# VCSEL.net
KiCad netlist of a schematic drawn in Altium Designer
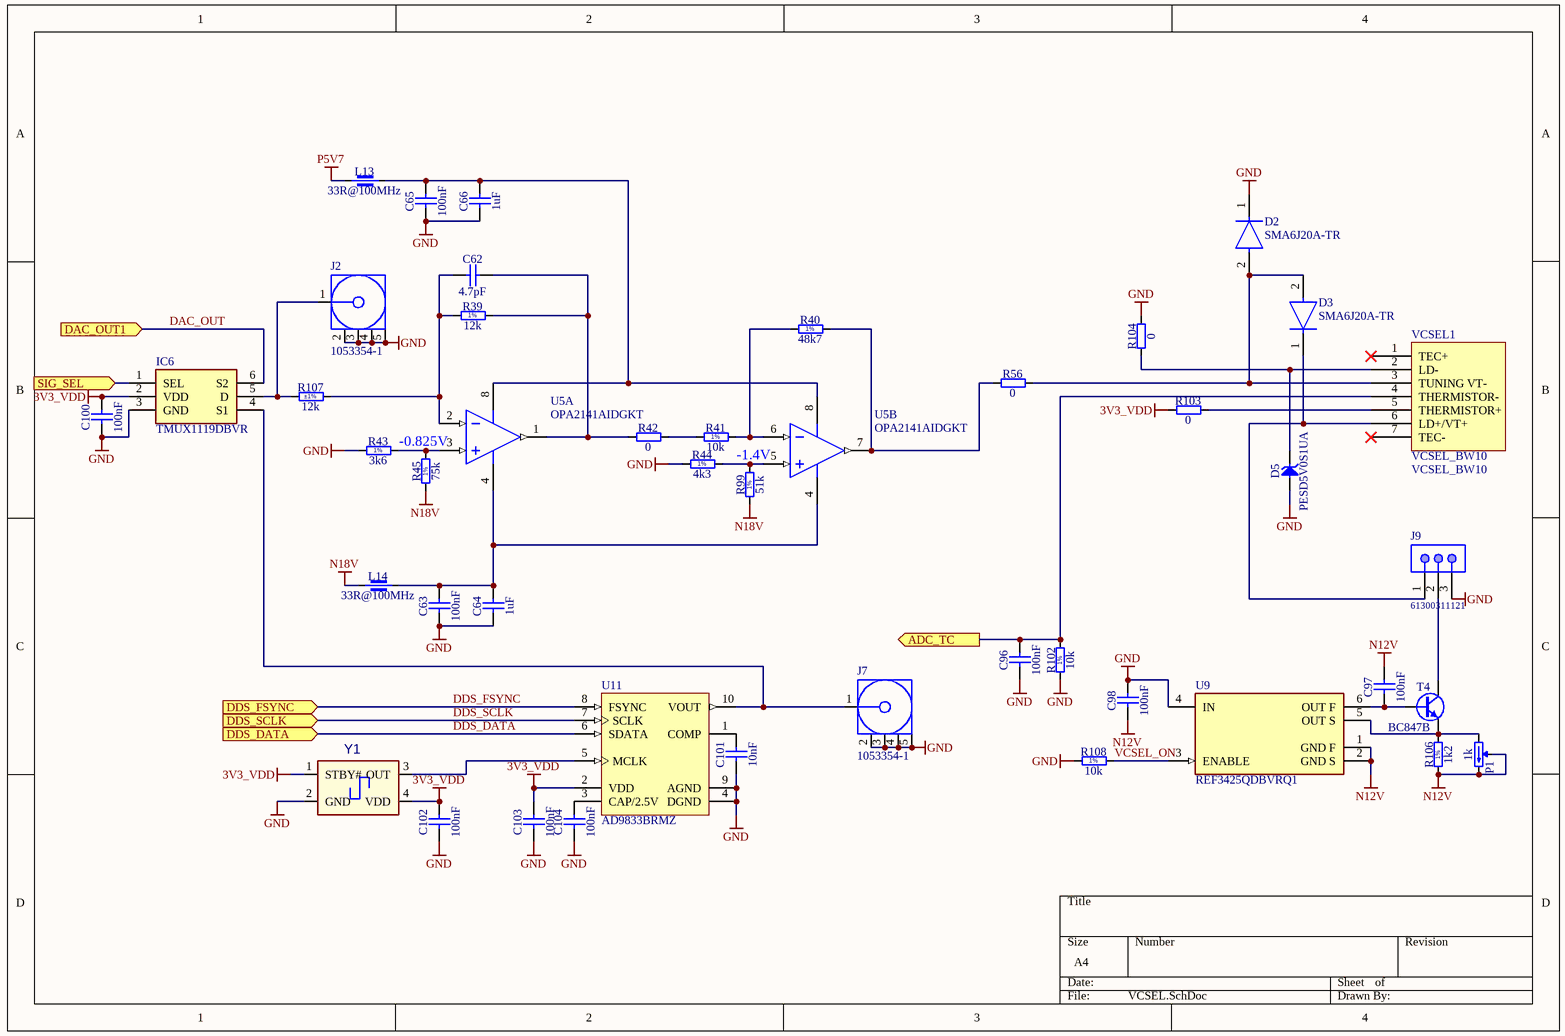
[diagram p0: VCSEL.SchDoc]

(export (version "E")
  (design (tool "Eeschema 10.0.6"))
  (components
    (comp (ref "C62")
      (value "4.7pF")
      (footprint "CAPC1005X70N")
      (description "Non-polarised capacitor")
      (fields
        (field (name "PART NUMBER") "CC0402_4.7PF_50V_0.25PF_C0G_VISHAY_VJ_NON-MAGNETIC")
        (field (name "VOLTAGE") "50V")
        (field (name "AUTHOR") "CERN DEM MR")
      )
      (libsource (lib "Capacitors") (part "Capacitor - non polarized"))
    )
    (comp (ref "C63")
      (value "100nF")
      (footprint "CAPC1608X87N")
      (description "Non-polarised capacitor")
      (fields
        (field (name "PART NUMBER") "CC0603_100NF_50V_10%_X5R")
        (field (name "VOLTAGE") "50V")
        (field (name "AUTHOR") "CERN DEM MR")
      )
      (libsource (lib "Capacitors") (part "Capacitor - non polarized"))
    )
    (comp (ref "C64")
      (value "1uF")
      (footprint "CAPC1608X87N")
      (description "Non-polarised capacitor")
      (fields
        (field (name "PART NUMBER") "CC0603_1UF_25V_10%_X7R")
        (field (name "VOLTAGE") "25V")
        (field (name "AUTHOR") "CERN DEM JLC")
      )
      (libsource (lib "Capacitors") (part "Capacitor - non polarized"))
    )
    (comp (ref "C65")
      (value "100nF")
      (footprint "CAPC1005X55N")
      (description "Non-polarised capacitor")
      (fields
        (field (name "PART NUMBER") "CC0402_100NF_16V_10%_X7R")
        (field (name "VOLTAGE") "16V")
        (field (name "AUTHOR") "CERN DEM JLC")
      )
      (libsource (lib "Capacitors") (part "Capacitor - non polarized"))
    )
    (comp (ref "C66")
      (value "1uF")
      (footprint "CAPC1005X55N")
      (description "Non-polarised capacitor")
      (fields
        (field (name "PART NUMBER") "CC0402_1UF_16V_10%_X5R")
        (field (name "VOLTAGE") "16V")
        (field (name "AUTHOR") "CERN DEM JLC")
      )
      (libsource (lib "Capacitors") (part "Capacitor - non polarized"))
    )
    (comp (ref "C96")
      (value "100nF")
      (footprint "CAPC1005X55N")
      (description "Non-polarised capacitor")
      (fields
        (field (name "PART NUMBER") "CC0402_100NF_16V_10%_X7R")
        (field (name "VOLTAGE") "16V")
        (field (name "AUTHOR") "CERN DEM JLC")
      )
      (libsource (lib "Capacitors") (part "Capacitor - non polarized"))
    )
    (comp (ref "C97")
      (value "100nF")
      (footprint "CAPC1005X55N")
      (description "Non-polarised capacitor")
      (fields
        (field (name "PART NUMBER") "CC0402_100NF_16V_10%_X7R")
        (field (name "VOLTAGE") "16V")
        (field (name "AUTHOR") "CERN DEM JLC")
      )
      (libsource (lib "Capacitors") (part "Capacitor - non polarized"))
    )
    (comp (ref "C98")
      (value "100nF")
      (footprint "CAPC1005X55N")
      (description "Non-polarised capacitor")
      (fields
        (field (name "PART NUMBER") "CC0402_100NF_16V_10%_X7R")
        (field (name "VOLTAGE") "16V")
        (field (name "AUTHOR") "CERN DEM JLC")
      )
      (libsource (lib "Capacitors") (part "Capacitor - non polarized"))
    )
    (comp (ref "C100")
      (value "100nF")
      (footprint "CAPC1005X55N")
      (description "Non-polarised capacitor")
      (fields
        (field (name "PART NUMBER") "CC0402_100NF_16V_10%_X7R")
        (field (name "VOLTAGE") "16V")
        (field (name "AUTHOR") "CERN DEM JLC")
      )
      (libsource (lib "Capacitors") (part "Capacitor - non polarized"))
    )
    (comp (ref "C101")
      (value "10nF")
      (footprint "CAPC1005X55N")
      (description "Non-polarised capacitor")
      (fields
        (field (name "PART NUMBER") "CC0402_10NF_16V_10%_X7R")
        (field (name "VOLTAGE") "16V")
        (field (name "AUTHOR") "CERN DEM JLC")
      )
      (libsource (lib "Capacitors") (part "Capacitor - non polarized"))
    )
    (comp (ref "C102")
      (value "100nF")
      (footprint "CAPC1005X55N")
      (description "Non-polarised capacitor")
      (fields
        (field (name "PART NUMBER") "CC0402_100NF_16V_10%_X7R")
        (field (name "VOLTAGE") "16V")
        (field (name "AUTHOR") "CERN DEM JLC")
      )
      (libsource (lib "Capacitors") (part "Capacitor - non polarized"))
    )
    (comp (ref "C103")
      (value "100nF")
      (footprint "CAPC1005X55N")
      (description "Non-polarised capacitor")
      (fields
        (field (name "PART NUMBER") "CC0402_100NF_16V_10%_X7R")
        (field (name "VOLTAGE") "16V")
        (field (name "AUTHOR") "CERN DEM JLC")
      )
      (libsource (lib "Capacitors") (part "Capacitor - non polarized"))
    )
    (comp (ref "C104")
      (value "100nF")
      (footprint "CAPC1005X55N")
      (description "Non-polarised capacitor")
      (fields
        (field (name "PART NUMBER") "CC0402_100NF_16V_10%_X7R")
        (field (name "VOLTAGE") "16V")
        (field (name "AUTHOR") "CERN DEM JLC")
      )
      (libsource (lib "Capacitors") (part "Capacitor - non polarized"))
    )
    (comp (ref "D2")
      (value "SMA6J20A-TR")
      (footprint "FP-SMA-MFG")
      (description "TVS DIODE 20V 36.8V SMA")
      (libsource (lib "Altium Content Vault") (part "d7152d700b627762746794eb795d46e"))
    )
    (comp (ref "D3")
      (value "SMA6J20A-TR")
      (footprint "FP-SMA-MFG")
      (description "TVS DIODE 20V 36.8V SMA")
      (libsource (lib "Altium Content Vault") (part "d7152d700b627762746794eb795d46e"))
    )
    (comp (ref "D5")
      (value "PESD5V0S1UA")
      (footprint "SOD2512X110N")
      (description "Transient Voltage Suppressor Diode (Uni-Directional)")
      (fields
        (field (name "VOLTAGE") "5V")
        (field (name "POWER") "890W")
        (field (name "AUTHOR") "CERN DEM JLC")
      )
      (libsource (lib "ICs And Semiconductors") (part "Diode TVS Uni-Directional"))
    )
    (comp (ref "IC6")
      (value "TMUX1119DBVR")
      (footprint "SamacSys:SOT95P280X145-6N")
      (description "Integrated Circuit")
      (libsource (lib "*") (part "TMUX1119DBVR"))
    )
    (comp (ref "J2")
      (value "1053354-1")
      (footprint "TECO-1053354-1_V")
      (description "Female Coaxial Connector, Pitch 2.55 mm, Height 9.5 mm, Tail Length 3.9 mm, RoHS, Bulk")
      (fields (field (name "MANUFACTURER") "TE Connectivity"))
      (libsource (lib "Altium Content Vault") (part "CN-S-4F-RF5"))
    )
    (comp (ref "J7")
      (value "1053354-1")
      (footprint "TECO-1053354-1_V")
      (description "Female Coaxial Connector, Pitch 2.55 mm, Height 9.5 mm, Tail Length 3.9 mm, RoHS, Bulk")
      (fields (field (name "MANUFACTURER") "TE Connectivity"))
      (libsource (lib "Altium Content Vault") (part "CN-S-4F-RF5"))
    )
    (comp (ref "J9")
      (value "61300311121")
      (footprint "61300311121")
      (description "WR-PHD Pin Header, THT, pitch 2.54mm, Single Row, Vertical, 3pin")
      (fields (field (name "PUBLISHER") "Wurth Elektronik"))
      (libsource (lib "ALTIUM-WR-PHD_PIN_HEADER_SOCKET_HEADER-rev19a") (part "61300311121"))
    )
    (comp (ref "L13")
      (value "33R@100MHz")
      (footprint "INDC1005X55N")
      (fields
        (field (name "PART NUMBER") "IND0402_MURATA_BLM15PX330SN1D")
        (field (name "POWER") "3A")
        (field (name "TOLERANCE") "±25%")
        (field (name "AUTHOR") "CERN DEM JMW")
      )
      (libsource (lib "Inductors & Transformers") (part "Ferrite Bead"))
    )
    (comp (ref "L14")
      (value "33R@100MHz")
      (footprint "INDC1005X55N")
      (fields
        (field (name "PART NUMBER") "IND0402_MURATA_BLM15PX330SN1D")
        (field (name "POWER") "3A")
        (field (name "TOLERANCE") "±25%")
        (field (name "AUTHOR") "CERN DEM JMW")
      )
      (libsource (lib "Inductors & Transformers") (part "Ferrite Bead"))
    )
    (comp (ref "P1")
      (value "1k")
      (footprint "TRIM_BOURNS_3266W")
      (description "Trimming Potentiometer")
      (fields
        (field (name "PART NUMBER") "TRIM_12T_1K_BOURNS_3266W-1-102LF")
        (field (name "POWER") "0.25W")
        (field (name "AUTHOR") "CERN DEM JLC")
      )
      (libsource (lib "Resistors") (part "Trimming Potentiometer"))
    )
    (comp (ref "R39")
      (value "12k")
      (footprint "RESC1005X40N")
      (description "Resistor - 1%")
      (fields
        (field (name "PART NUMBER") "R0402_12K_1%_0.0625W_100PPM")
        (field (name "POWER") "0.0625W")
        (field (name "AUTHOR") "CERN DEM JLC")
      )
      (libsource (lib "Resistors") (part "Resistor - 1%"))
    )
    (comp (ref "R40")
      (value "48k7")
      (footprint "RESC1608X55N")
      (description "Resistor - 1%")
      (fields
        (field (name "PART NUMBER") "R0603_48K7_1%_0.1W_100PPM")
        (field (name "POWER") "0.1W")
        (field (name "AUTHOR") "CERN DEM JLC")
      )
      (libsource (lib "") (part "Resistor - 1%_1"))
    )
    (comp (ref "R41")
      (value "10k")
      (footprint "RESC1005X40N")
      (description "Resistor - 1%")
      (fields
        (field (name "PART NUMBER") "R0402_10K_1%_0.0625W_100PPM")
        (field (name "POWER") "0.0625W")
        (field (name "AUTHOR") "CERN DEM JLC")
      )
      (libsource (lib "Resistors") (part "Resistor - 1%"))
    )
    (comp (ref "R42")
      (value "0")
      (footprint "RESC1005X40N")
      (description "Resistor")
      (fields
        (field (name "PART NUMBER") "R0402_0R_JUMPER")
        (field (name "MANUFACTURER") "GENERIC")
        (field (name "AUTHOR") "CERN DEM JLC")
      )
      (libsource (lib "Resistors") (part "Resistor"))
    )
    (comp (ref "R43")
      (value "3k6")
      (footprint "RESC1005X40N")
      (description "Resistor - 1%")
      (fields
        (field (name "PART NUMBER") "R0402_3K6_1%_0.0625W_100PPM")
        (field (name "POWER") "0.0625W")
        (field (name "AUTHOR") "CERN DEM JLC")
      )
      (libsource (lib "Resistors") (part "Resistor - 1%"))
    )
    (comp (ref "R44")
      (value "4k3")
      (footprint "RESC1005X40N")
      (description "Resistor - 1%")
      (fields
        (field (name "PART NUMBER") "R0402_4K3_1%_0.0625W_100PPM")
        (field (name "POWER") "0.0625W")
        (field (name "AUTHOR") "CERN DEM JLC")
      )
      (libsource (lib "Resistors") (part "Resistor - 1%"))
    )
    (comp (ref "R45")
      (value "75k")
      (footprint "RESC1005X40N")
      (description "Resistor - 1%")
      (fields
        (field (name "PART NUMBER") "R0402_75K_1%_0.0625W_100PPM")
        (field (name "POWER") "0.0625W")
        (field (name "AUTHOR") "CERN DEM JLC")
      )
      (libsource (lib "Resistors") (part "Resistor - 1%"))
    )
    (comp (ref "R56")
      (value "0")
      (footprint "RESC1005X40N")
      (description "Resistor")
      (fields
        (field (name "PART NUMBER") "R0402_0R_JUMPER")
        (field (name "MANUFACTURER") "GENERIC")
        (field (name "AUTHOR") "CERN DEM JLC")
      )
      (libsource (lib "Resistors") (part "Resistor"))
    )
    (comp (ref "R99")
      (value "51k")
      (footprint "RESC1005X40N")
      (description "Resistor - 1%")
      (fields
        (field (name "PART NUMBER") "R0402_51K_1%_0.0625W_100PPM")
        (field (name "POWER") "0.0625W")
        (field (name "AUTHOR") "CERN DEM JLC")
      )
      (libsource (lib "Resistors") (part "Resistor - 1%"))
    )
    (comp (ref "R102")
      (value "10k")
      (footprint "RESC1005X40N")
      (description "Resistor - 1%")
      (fields
        (field (name "PART NUMBER") "R0402_10K_1%_0.0625W_100PPM")
        (field (name "POWER") "0.0625W")
        (field (name "AUTHOR") "CERN DEM JLC")
      )
      (libsource (lib "Resistors") (part "Resistor - 1%"))
    )
    (comp (ref "R103")
      (value "0")
      (footprint "RESC1005X40N")
      (description "Resistor")
      (fields
        (field (name "PART NUMBER") "R0402_0R_JUMPER")
        (field (name "MANUFACTURER") "GENERIC")
        (field (name "AUTHOR") "CERN DEM JLC")
      )
      (libsource (lib "Resistors") (part "Resistor"))
    )
    (comp (ref "R104")
      (value "0")
      (footprint "RESC1005X40N")
      (description "Resistor")
      (fields
        (field (name "PART NUMBER") "R0402_0R_JUMPER")
        (field (name "MANUFACTURER") "GENERIC")
        (field (name "AUTHOR") "CERN DEM JLC")
      )
      (libsource (lib "Resistors") (part "Resistor"))
    )
    (comp (ref "R106")
      (value "1k2")
      (footprint "RESC1005X40N")
      (description "Resistor - 1%")
      (fields
        (field (name "PART NUMBER") "R0402_1K2_1%_0.0625W_100PPM")
        (field (name "POWER") "0.0625W")
        (field (name "AUTHOR") "CERN DEM JLC")
      )
      (libsource (lib "Resistors") (part "Resistor - 1%"))
    )
    (comp (ref "R107")
      (value "12k")
      (footprint "RESC1005X40N")
      (description "Resistor - 1%")
      (fields
        (field (name "PART NUMBER") "R0402_12K_1%_0.0625W_100PPM")
        (field (name "MANUFACTURER") "GENERIC")
        (field (name "TOLERANCE") "±1%")
        (field (name "AUTHOR") "CERN DEM JLC")
      )
      (libsource (lib "Resistors") (part "Resistor - 1%"))
    )
    (comp (ref "R108")
      (value "10k")
      (footprint "RESC1005X40N")
      (description "Resistor - 1%")
      (fields
        (field (name "PART NUMBER") "R0402_10K_1%_0.0625W_100PPM")
        (field (name "POWER") "0.0625W")
        (field (name "AUTHOR") "CERN DEM JLC")
      )
      (libsource (lib "Resistors") (part "Resistor - 1%"))
    )
    (comp (ref "T4")
      (value "BC847B")
      (footprint "SOT95P230X110-3N")
      (description "NPN Transistor")
      (fields (field (name "MANUFACTURER") "NXP SEMICONDUCTORS") (field (name "AUTHOR") "CERN DEM JLC"))
      (libsource (lib "ICs And Semiconductors") (part "NPN B1 E2 C3"))
    )
    (comp (ref "U5")
      (value "OPA2141AIDGKT")
      (footprint "DGK0008A_M")
      (fields (field (name "MANUFACTURER") "Texas Instruments"))
      (libsource (lib "Altium Content Vault") (part "TI-OPA-8_2"))
    )
    (comp (ref "U9")
      (value "REF3425QDBVRQ1")
      (footprint "FP-DBV0006A-MFG")
      (description "IC VREF SERIES 0.05% SOT23-6")
      (fields
        (field (name "OCTOPART") "https://octopart.com/ref3433qdbvrq1-texas+instruments-95842010")
        (field (name "MANUFACTURER") "Texas Instruments")
      )
      (libsource (lib "Altium Content Vault") (part "852d3c1243c2caefb114a4c8e829102"))
    )
    (comp (ref "U11")
      (value "AD9833BRMZ")
      (footprint "ADI-RM-10_M")
      (libsource (lib "Altium Content Vault") (part "ADI-AD9833-RM-10"))
    )
    (comp (ref "VCSEL1")
      (value "VCSEL_BW10")
      (footprint "VCSEL_BW10")
      (libsource (lib "MG_lib") (part "VCSLE_BW10"))
    )
    (comp (ref "Y1")
      (value "OSCILLATOR_4P_nSTBY")
      (footprint "OSCILLATOR_CDFN_L2.5W2.0H0.85")
      (fields (field (name "OWNER") "Sam Charles"))
      (libsource (lib "MCHP-CDB") (part "OSCILLATOR_4P_nSTBY"))
    )
  )
  (nets
    (net (code "1") (name "/ADC_TC") (class "Default")
      (node (ref "C96") (pin "2") (pinfunction "2_2") (pintype "passive"))
      (node (ref "R102") (pin "2") (pinfunction "2_2") (pintype "passive"))
      (node (ref "VCSEL1") (pin "4") (pinfunction "THERMISTOR-_4") (pintype "passive"))
    )
    (net (code "2") (name "/DAC_OUT") (class "Default")
      (node (ref "IC6") (pin "6") (pinfunction "S2_6") (pintype "passive"))
    )
    (net (code "3") (name "/DDS_DATA") (class "Default")
      (node (ref "U11") (pin "6") (pinfunction "SDATA_6") (pintype "input"))
    )
    (net (code "4") (name "/DDS_FSYNC") (class "Default")
      (node (ref "U11") (pin "8") (pinfunction "FSYNC_8") (pintype "input"))
    )
    (net (code "5") (name "/DDS_SCLK") (class "Default")
      (node (ref "U11") (pin "7") (pinfunction "SCLK_7") (pintype "input"))
    )
    (net (code "6") (name "/SIG_SEL") (class "Default")
      (node (ref "IC6") (pin "1") (pinfunction "SEL_1") (pintype "passive"))
    )
    (net (code "7") (name "/VCSEL_ON") (class "Default")
      (node (ref "R108") (pin "2") (pinfunction "2_2") (pintype "passive"))
      (node (ref "U9") (pin "3") (pinfunction "ENABLE_3") (pintype "input"))
    )
    (net (code "8") (name "3V3_VDD") (class "Default")
      (node (ref "C100") (pin "2") (pinfunction "2_2") (pintype "passive"))
      (node (ref "C102") (pin "2") (pinfunction "2_2") (pintype "passive"))
      (node (ref "C103") (pin "2") (pinfunction "2_2") (pintype "passive"))
      (node (ref "IC6") (pin "2") (pinfunction "VDD_2") (pintype "passive"))
      (node (ref "R103") (pin "1") (pinfunction "1_1") (pintype "passive"))
      (node (ref "U11") (pin "2") (pinfunction "VDD_2") (pintype "power_in"))
      (node (ref "Y1") (pin "1") (pinfunction "STBY#_1") (pintype "passive"))
      (node (ref "Y1") (pin "4") (pinfunction "VDD_4") (pintype "passive"))
    )
    (net (code "9") (name "GND") (class "Default")
      (node (ref "C100") (pin "1") (pinfunction "1_1") (pintype "passive"))
      (node (ref "C101") (pin "1") (pinfunction "1_1") (pintype "passive"))
      (node (ref "C102") (pin "1") (pinfunction "1_1") (pintype "passive"))
      (node (ref "C103") (pin "1") (pinfunction "1_1") (pintype "passive"))
      (node (ref "C104") (pin "1") (pinfunction "1_1") (pintype "passive"))
      (node (ref "C63") (pin "1") (pinfunction "1_1") (pintype "passive"))
      (node (ref "C64") (pin "1") (pinfunction "1_1") (pintype "passive"))
      (node (ref "C65") (pin "1") (pinfunction "1_1") (pintype "passive"))
      (node (ref "C66") (pin "1") (pinfunction "1_1") (pintype "passive"))
      (node (ref "C96") (pin "1") (pinfunction "1_1") (pintype "passive"))
      (node (ref "C98") (pin "2") (pinfunction "2_2") (pintype "passive"))
      (node (ref "D2") (pin "1") (pinfunction "C_1") (pintype "passive"))
      (node (ref "D5") (pin "2") (pinfunction "A_2") (pintype "passive"))
      (node (ref "IC6") (pin "3") (pinfunction "GND_3") (pintype "passive"))
      (node (ref "J2") (pin "2") (pinfunction "2_2") (pintype "passive"))
      (node (ref "J2") (pin "3") (pinfunction "3_3") (pintype "passive"))
      (node (ref "J2") (pin "4") (pinfunction "4_4") (pintype "passive"))
      (node (ref "J2") (pin "5") (pinfunction "5_5") (pintype "passive"))
      (node (ref "J7") (pin "2") (pinfunction "2_2") (pintype "passive"))
      (node (ref "J7") (pin "3") (pinfunction "3_3") (pintype "passive"))
      (node (ref "J7") (pin "4") (pinfunction "4_4") (pintype "passive"))
      (node (ref "J7") (pin "5") (pinfunction "5_5") (pintype "passive"))
      (node (ref "J9") (pin "3") (pinfunction "3_3") (pintype "passive"))
      (node (ref "R102") (pin "1") (pinfunction "1_1") (pintype "passive"))
      (node (ref "R104") (pin "2") (pinfunction "2_2") (pintype "passive"))
      (node (ref "R108") (pin "1") (pinfunction "1_1") (pintype "passive"))
      (node (ref "R43") (pin "1") (pinfunction "1_1") (pintype "passive"))
      (node (ref "R44") (pin "1") (pinfunction "1_1") (pintype "passive"))
      (node (ref "U11") (pin "4") (pinfunction "DGND_4") (pintype "power_in"))
      (node (ref "U11") (pin "9") (pinfunction "AGND_9") (pintype "power_in"))
      (node (ref "U9") (pin "4") (pinfunction "IN_4") (pintype "power_in"))
      (node (ref "Y1") (pin "2") (pinfunction "GND_2") (pintype "passive"))
    )
    (net (code "10") (name "N12V") (class "Default")
      (node (ref "C97") (pin "2") (pinfunction "2_2") (pintype "passive"))
      (node (ref "C98") (pin "1") (pinfunction "1_1") (pintype "passive"))
      (node (ref "P1") (pin "2") (pinfunction "W_2") (pintype "passive"))
      (node (ref "P1") (pin "3") (pinfunction "CW_3") (pintype "passive"))
      (node (ref "R106") (pin "1") (pinfunction "1_1") (pintype "passive"))
      (node (ref "U9") (pin "1") (pinfunction "GND_F_1") (pintype "power_in"))
      (node (ref "U9") (pin "2") (pinfunction "GND_S_2") (pintype "power_in"))
    )
    (net (code "11") (name "N18V") (class "Default")
      (node (ref "L14") (pin "1") (pinfunction "1_1") (pintype "passive"))
      (node (ref "R45") (pin "1") (pinfunction "1_1") (pintype "passive"))
      (node (ref "R99") (pin "1") (pinfunction "1_1") (pintype "passive"))
    )
    (net (code "12") (name "Net-(D2-A)") (class "Default")
      (node (ref "D2") (pin "2") (pinfunction "A_2") (pintype "passive"))
      (node (ref "D3") (pin "2") (pinfunction "A_2") (pintype "passive"))
      (node (ref "R56") (pin "2") (pinfunction "2_2") (pintype "passive"))
      (node (ref "VCSEL1") (pin "3") (pinfunction "TUNING_VT-_3") (pintype "passive"))
    )
    (net (code "13") (name "Net-(D3-C)") (class "Default")
      (node (ref "D3") (pin "1") (pinfunction "C_1") (pintype "passive"))
      (node (ref "J9") (pin "1") (pinfunction "1_1") (pintype "passive"))
      (node (ref "VCSEL1") (pin "6") (pinfunction "LD+/VT+_6") (pintype "passive"))
    )
    (net (code "14") (name "Net-(D5-C)") (class "Default")
      (node (ref "D5") (pin "1") (pinfunction "C_1") (pintype "passive"))
      (node (ref "R104") (pin "1") (pinfunction "1_1") (pintype "passive"))
      (node (ref "VCSEL1") (pin "2") (pinfunction "LD-_2") (pintype "passive"))
    )
    (net (code "15") (name "Net-(IC6-D)") (class "Default")
      (node (ref "IC6") (pin "5") (pinfunction "D_5") (pintype "passive"))
      (node (ref "J2") (pin "1") (pinfunction "1_1") (pintype "passive"))
      (node (ref "R107") (pin "1") (pinfunction "1_1") (pintype "passive"))
    )
    (net (code "16") (name "Net-(IC6-S1)") (class "Default")
      (node (ref "IC6") (pin "4") (pinfunction "S1_4") (pintype "passive"))
      (node (ref "J7") (pin "1") (pinfunction "1_1") (pintype "passive"))
      (node (ref "U11") (pin "10") (pinfunction "VOUT_10") (pintype "output"))
    )
    (net (code "17") (name "Net-(P1-CCW)") (class "Default")
      (node (ref "P1") (pin "1") (pinfunction "CCW_1") (pintype "passive"))
      (node (ref "R106") (pin "2") (pinfunction "2_2") (pintype "passive"))
      (node (ref "T4") (pin "2") (pinfunction "E_2") (pintype "passive"))
      (node (ref "U9") (pin "5") (pinfunction "OUT_S_5") (pintype "power_in"))
    )
    (net (code "18") (name "Net-(R41-Pad1)") (class "Default")
      (node (ref "R41") (pin "1") (pinfunction "1_1") (pintype "passive"))
      (node (ref "R42") (pin "2") (pinfunction "2_2") (pintype "passive"))
    )
    (net (code "19") (name "Net-(T4-B)") (class "Default")
      (node (ref "C97") (pin "1") (pinfunction "1_1") (pintype "passive"))
      (node (ref "T4") (pin "1") (pinfunction "B_1") (pintype "passive"))
      (node (ref "U9") (pin "6") (pinfunction "OUT_F_6") (pintype "power_in"))
    )
    (net (code "20") (name "Net-(T4-C)") (class "Default")
      (node (ref "J9") (pin "2") (pinfunction "2_2") (pintype "passive"))
      (node (ref "T4") (pin "3") (pinfunction "C_3") (pintype "passive"))
    )
    (net (code "21") (name "Net-(U5A-IN_A+)") (class "Default")
      (node (ref "R43") (pin "2") (pinfunction "2_2") (pintype "passive"))
      (node (ref "R45") (pin "2") (pinfunction "2_2") (pintype "passive"))
      (node (ref "U5") (pin "3") (pinfunction "IN_A+_3") (pintype "input"))
    )
    (net (code "22") (name "Net-(U5A-IN_A-)") (class "Default")
      (node (ref "C62") (pin "1") (pinfunction "1_1") (pintype "passive"))
      (node (ref "R107") (pin "2") (pinfunction "2_2") (pintype "passive"))
      (node (ref "R39") (pin "1") (pinfunction "1_1") (pintype "passive"))
      (node (ref "U5") (pin "2") (pinfunction "IN_A-_2") (pintype "input"))
    )
    (net (code "23") (name "Net-(U5A-OUT_A)") (class "Default")
      (node (ref "C62") (pin "2") (pinfunction "2_2") (pintype "passive"))
      (node (ref "R39") (pin "2") (pinfunction "2_2") (pintype "passive"))
      (node (ref "R42") (pin "1") (pinfunction "1_1") (pintype "passive"))
      (node (ref "U5") (pin "1") (pinfunction "OUT_A_1") (pintype "output"))
    )
    (net (code "24") (name "Net-(U5A-V+)") (class "Default")
      (node (ref "C65") (pin "2") (pinfunction "2_2") (pintype "passive"))
      (node (ref "C66") (pin "2") (pinfunction "2_2") (pintype "passive"))
      (node (ref "L13") (pin "2") (pinfunction "2_2") (pintype "passive"))
      (node (ref "U5") (pin "8") (pinfunction "V+_8") (pintype "power_in"))
    )
    (net (code "25") (name "Net-(U5A-V-)") (class "Default")
      (node (ref "C63") (pin "2") (pinfunction "2_2") (pintype "passive"))
      (node (ref "C64") (pin "2") (pinfunction "2_2") (pintype "passive"))
      (node (ref "L14") (pin "2") (pinfunction "2_2") (pintype "passive"))
      (node (ref "U5") (pin "4") (pinfunction "V-_4") (pintype "power_in"))
    )
    (net (code "26") (name "Net-(U5B-IN_B+)") (class "Default")
      (node (ref "R44") (pin "2") (pinfunction "2_2") (pintype "passive"))
      (node (ref "R99") (pin "2") (pinfunction "2_2") (pintype "passive"))
      (node (ref "U5") (pin "5") (pinfunction "IN_B+_5") (pintype "input"))
    )
    (net (code "27") (name "Net-(U5B-IN_B-)") (class "Default")
      (node (ref "R40") (pin "1") (pinfunction "1_1") (pintype "passive"))
      (node (ref "R41") (pin "2") (pinfunction "2_2") (pintype "passive"))
      (node (ref "U5") (pin "6") (pinfunction "IN_B-_6") (pintype "input"))
    )
    (net (code "28") (name "Net-(U5B-OUT_B)") (class "Default")
      (node (ref "R40") (pin "2") (pinfunction "2_2") (pintype "passive"))
      (node (ref "R56") (pin "1") (pinfunction "1_1") (pintype "passive"))
      (node (ref "U5") (pin "7") (pinfunction "OUT_B_7") (pintype "output"))
    )
    (net (code "29") (name "Net-(U11-CAP{slash}2.5V)") (class "Default")
      (node (ref "C104") (pin "2") (pinfunction "2_2") (pintype "passive"))
      (node (ref "U11") (pin "3") (pinfunction "CAP/2.5V_3") (pintype "power_in"))
    )
    (net (code "30") (name "Net-(U11-COMP)") (class "Default")
      (node (ref "C101") (pin "2") (pinfunction "2_2") (pintype "passive"))
      (node (ref "U11") (pin "1") (pinfunction "COMP_1") (pintype "passive"))
    )
    (net (code "31") (name "Net-(U11-MCLK)") (class "Default")
      (node (ref "U11") (pin "5") (pinfunction "MCLK_5") (pintype "input"))
      (node (ref "Y1") (pin "3") (pinfunction "OUT_3") (pintype "passive"))
    )
    (net (code "32") (name "Net-(VCSEL1-THERMISTOR+)") (class "Default")
      (node (ref "R103") (pin "2") (pinfunction "2_2") (pintype "passive"))
      (node (ref "VCSEL1") (pin "5") (pinfunction "THERMISTOR+_5") (pintype "passive"))
    )
    (net (code "33") (name "P5V7") (class "Default")
      (node (ref "L13") (pin "1") (pinfunction "1_1") (pintype "passive"))
    )
    (net (code "34") (name "unconnected-(VCSEL1-TEC+-Pad1)") (class "Default")
      (node (ref "VCSEL1") (pin "1") (pinfunction "TEC+_1") (pintype "passive+no_connect"))
    )
    (net (code "35") (name "unconnected-(VCSEL1-TEC--Pad7)") (class "Default")
      (node (ref "VCSEL1") (pin "7") (pinfunction "TEC-_7") (pintype "passive+no_connect"))
    )
  )
)
